# DM1092_TopLevel.net
KiCad netlist of a schematic drawn in Altium Designer
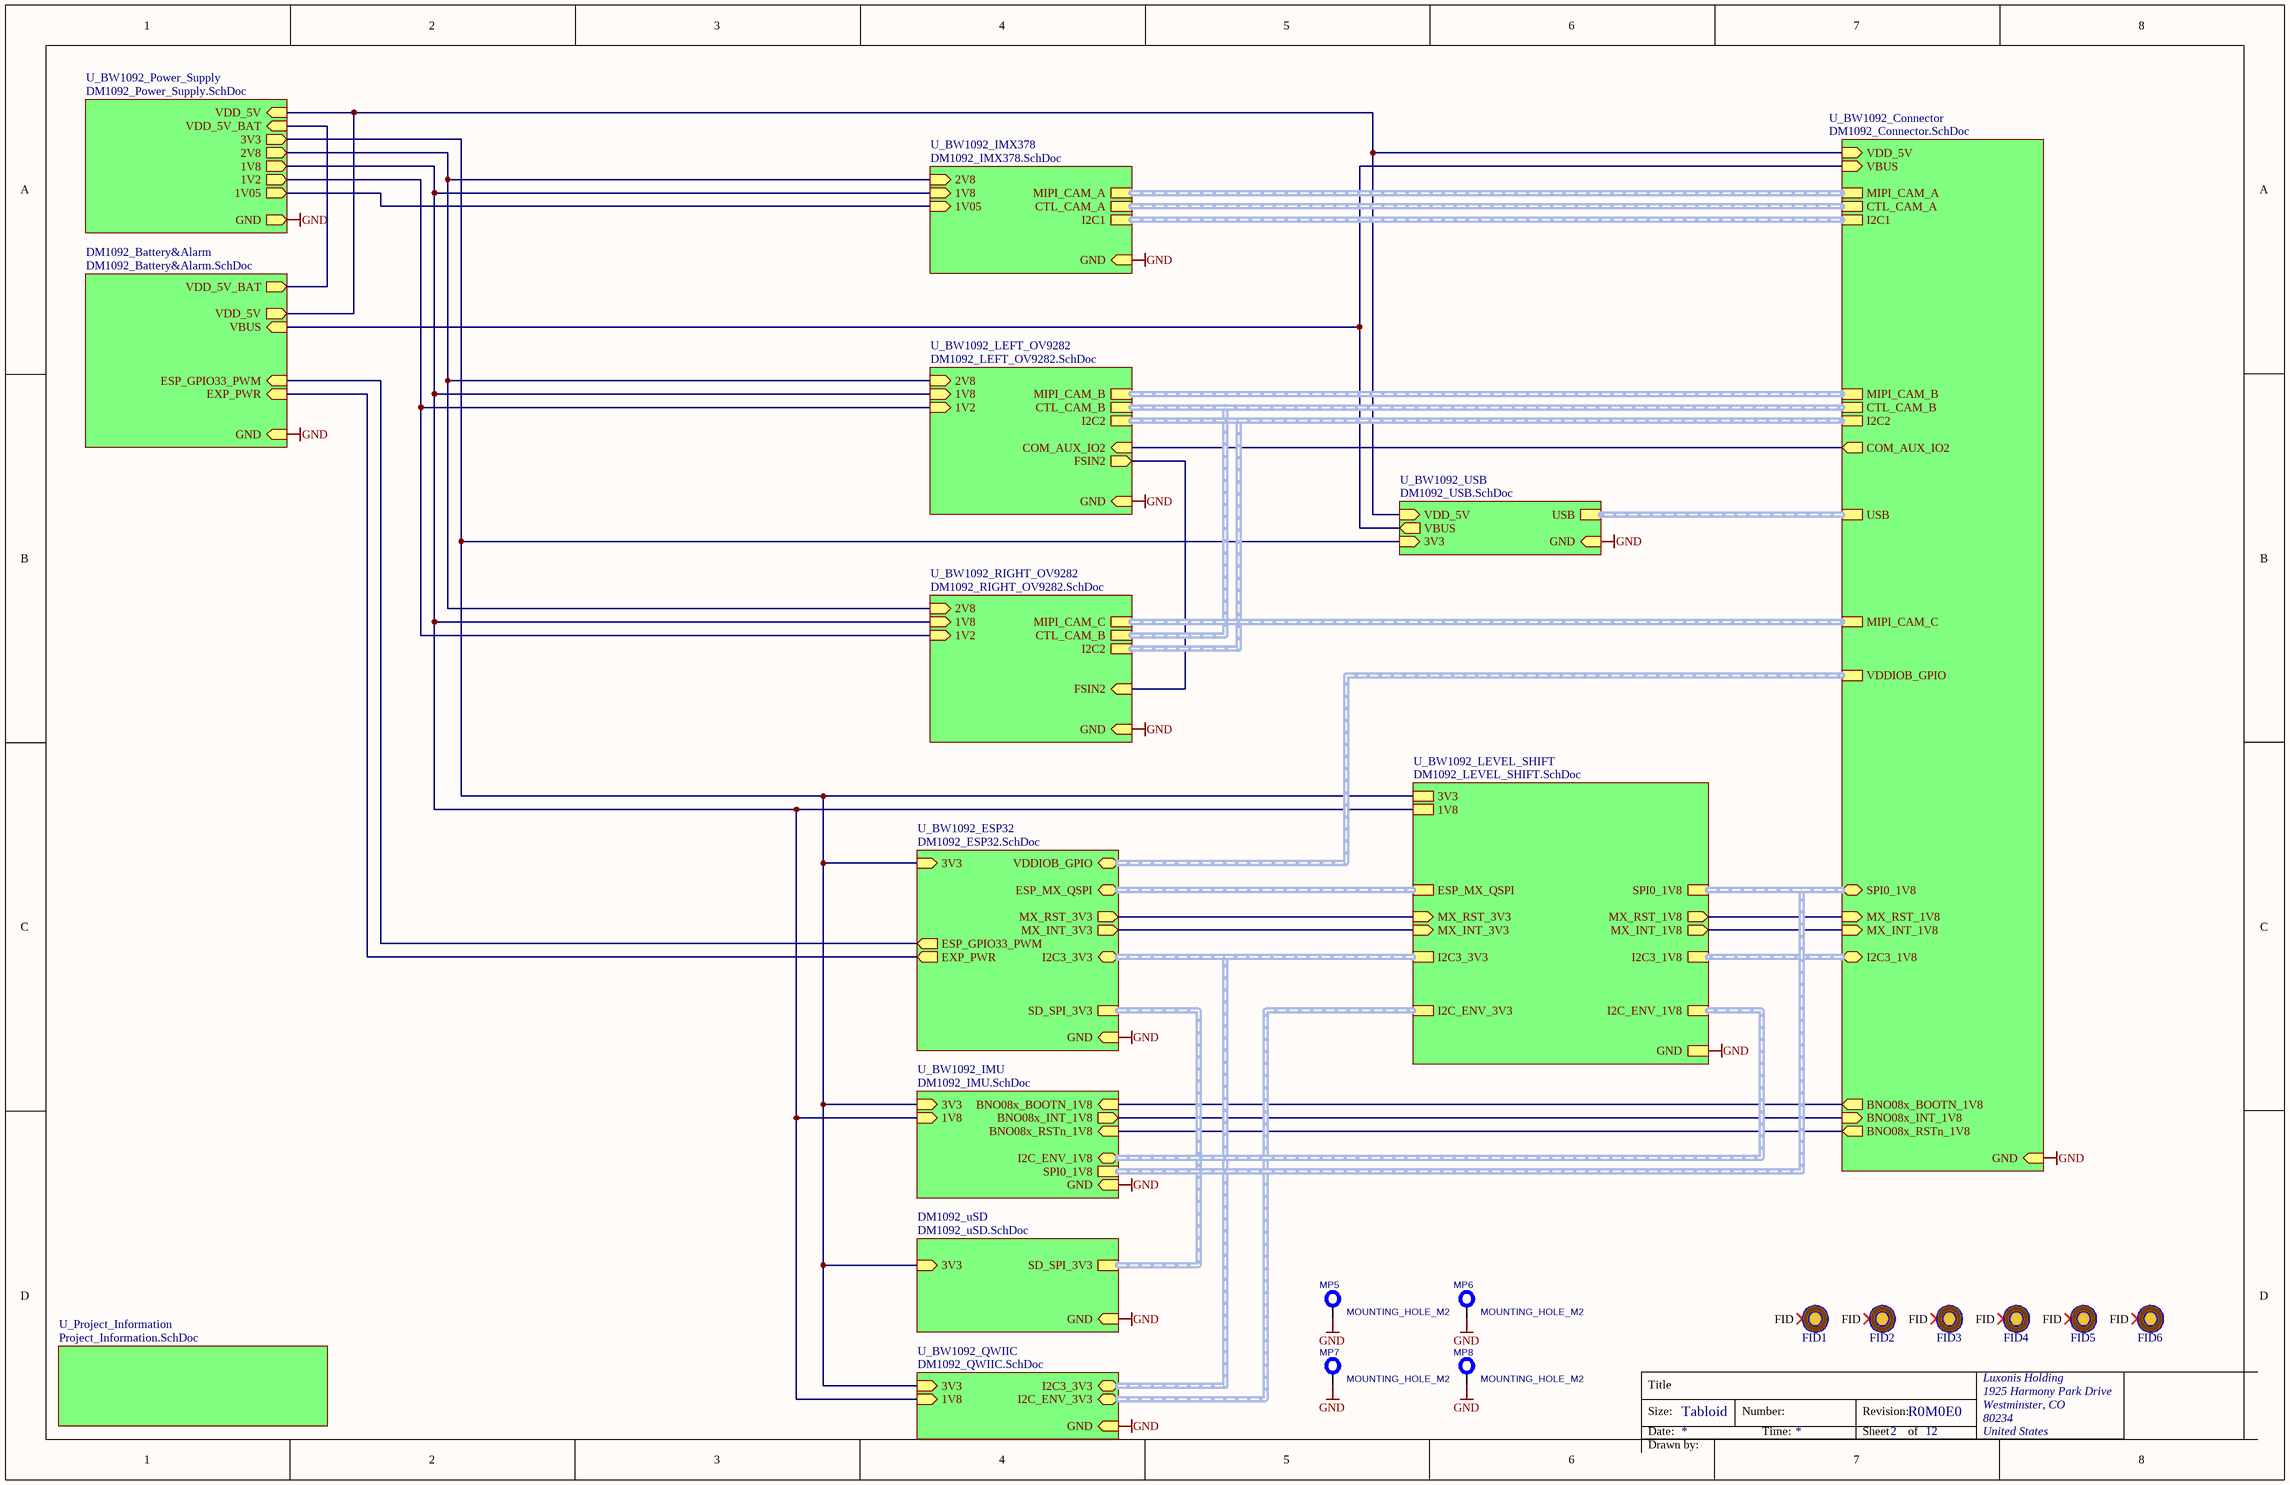
[diagram p0: DM1092_TopLevel.SchDoc]

(export (version "E")
  (design (tool "Eeschema 10.0.6"))
  (components
    (comp (ref "FID1")
      (value "FIDUCIAL_ROUND_1MM")
      (footprint "LuxonisMaster:FIDUCIAL_ROUND_1MM")
      (description "Fiducial with various available footprints")
      (libsource (lib "LuxonisMaster") (part "FIDUCIAL"))
    )
    (comp (ref "FID2")
      (value "FIDUCIAL_ROUND_1MM")
      (footprint "LuxonisMaster:FIDUCIAL_ROUND_1MM")
      (description "Fiducial with various available footprints")
      (libsource (lib "LuxonisMaster") (part "FIDUCIAL"))
    )
    (comp (ref "FID3")
      (value "FIDUCIAL_ROUND_1MM")
      (footprint "LuxonisMaster:FIDUCIAL_ROUND_1MM")
      (description "Fiducial with various available footprints")
      (libsource (lib "LuxonisMaster") (part "FIDUCIAL"))
    )
    (comp (ref "FID4")
      (value "FIDUCIAL_ROUND_1MM")
      (footprint "LuxonisMaster:FIDUCIAL_ROUND_1MM")
      (description "Fiducial with various available footprints")
      (libsource (lib "LuxonisMaster") (part "FIDUCIAL"))
    )
    (comp (ref "FID5")
      (value "FIDUCIAL_ROUND_1MM")
      (footprint "LuxonisMaster:FIDUCIAL_ROUND_1MM")
      (description "Fiducial with various available footprints")
      (libsource (lib "LuxonisMaster") (part "FIDUCIAL"))
    )
    (comp (ref "FID6")
      (value "FIDUCIAL_ROUND_1MM")
      (footprint "LuxonisMaster:FIDUCIAL_ROUND_1MM")
      (description "Fiducial with various available footprints")
      (libsource (lib "LuxonisMaster") (part "FIDUCIAL"))
    )
    (comp (ref "MP5")
      (value "MOUNTING_HOLE_M2")
      (footprint "LuxonisMaster:MOUNTING_HOLE_M2")
      (description "=CurrentFootprint")
      (libsource (lib "LuxonisMaster") (part "MP_Mounting-Holes"))
    )
    (comp (ref "MP6")
      (value "MOUNTING_HOLE_M2")
      (footprint "LuxonisMaster:MOUNTING_HOLE_M2")
      (description "=CurrentFootprint")
      (libsource (lib "LuxonisMaster") (part "MP_Mounting-Holes"))
    )
    (comp (ref "MP7")
      (value "MOUNTING_HOLE_M2")
      (footprint "LuxonisMaster:MOUNTING_HOLE_M2")
      (description "=CurrentFootprint")
      (libsource (lib "LuxonisMaster") (part "MP_Mounting-Holes"))
    )
    (comp (ref "MP8")
      (value "MOUNTING_HOLE_M2")
      (footprint "LuxonisMaster:MOUNTING_HOLE_M2")
      (description "=CurrentFootprint")
      (libsource (lib "LuxonisMaster") (part "MP_Mounting-Holes"))
    )
  )
  (nets
    (net (code "36") (name "GND") (class "Default")
      (node (ref "MP5") (pin "1") (pintype "passive"))
      (node (ref "MP6") (pin "1") (pintype "passive"))
      (node (ref "MP7") (pin "1") (pintype "passive"))
      (node (ref "MP8") (pin "1") (pintype "passive"))
    )
    (net (code "37") (name "unconnected-(FID1-PadFID)") (class "Default")
      (node (ref "FID1") (pin "FID") (pinfunction "FID_FID") (pintype "input+no_connect"))
    )
    (net (code "38") (name "unconnected-(FID2-PadFID)") (class "Default")
      (node (ref "FID2") (pin "FID") (pinfunction "FID_FID") (pintype "input+no_connect"))
    )
    (net (code "39") (name "unconnected-(FID3-PadFID)") (class "Default")
      (node (ref "FID3") (pin "FID") (pinfunction "FID_FID") (pintype "input+no_connect"))
    )
    (net (code "40") (name "unconnected-(FID4-PadFID)") (class "Default")
      (node (ref "FID4") (pin "FID") (pinfunction "FID_FID") (pintype "input+no_connect"))
    )
    (net (code "41") (name "unconnected-(FID5-PadFID)") (class "Default")
      (node (ref "FID5") (pin "FID") (pinfunction "FID_FID") (pintype "input+no_connect"))
    )
    (net (code "42") (name "unconnected-(FID6-PadFID)") (class "Default")
      (node (ref "FID6") (pin "FID") (pinfunction "FID_FID") (pintype "input+no_connect"))
    )
  )
)
